# Ring_3_B.net
KiCad netlist of a schematic drawn in Altium Designer
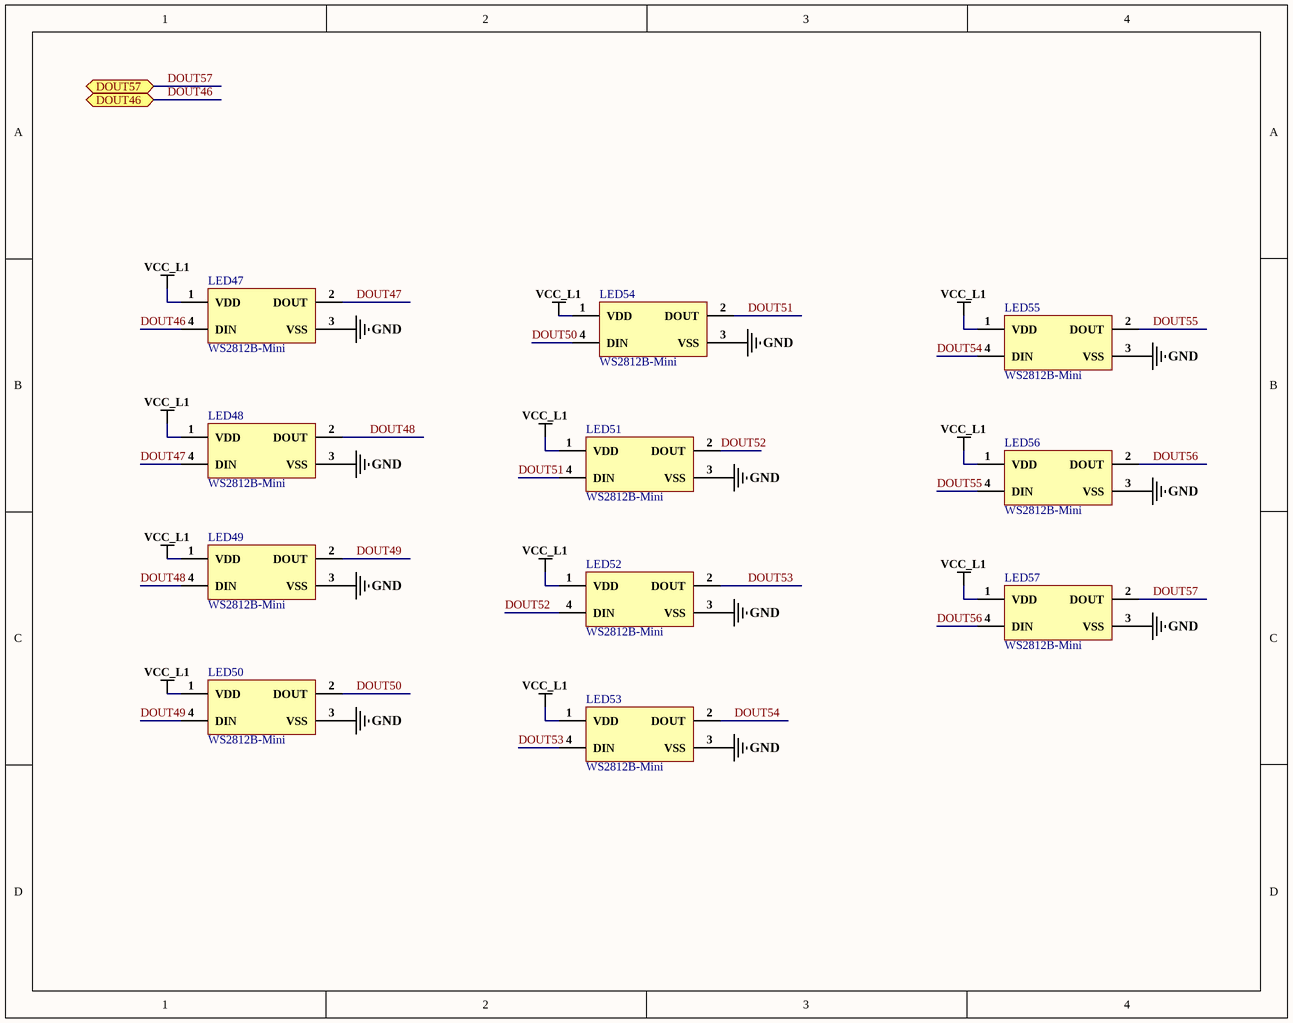
[diagram p0: Ring 3_B.SchDoc]

(export (version "E")
  (design (tool "Eeschema 10.0.6"))
  (components
    (comp (ref "LED47")
      (value "WS2812B-Mini")
      (footprint "WS2812B-Mini")
      (description "SMD,3.5x3.5mm Light Emitting Diodes (LED) RoHS")
      (fields (field (name "MANUFACTURER") "Worldsemi"))
      (libsource (lib "TT_IntLib") (part "WS2812B-Mini"))
    )
    (comp (ref "LED48")
      (value "WS2812B-Mini")
      (footprint "WS2812B-Mini")
      (description "SMD,3.5x3.5mm Light Emitting Diodes (LED) RoHS")
      (fields (field (name "MANUFACTURER") "Worldsemi"))
      (libsource (lib "TT_IntLib") (part "WS2812B-Mini"))
    )
    (comp (ref "LED49")
      (value "WS2812B-Mini")
      (footprint "WS2812B-Mini")
      (description "SMD,3.5x3.5mm Light Emitting Diodes (LED) RoHS")
      (fields (field (name "MANUFACTURER") "Worldsemi"))
      (libsource (lib "TT_IntLib") (part "WS2812B-Mini"))
    )
    (comp (ref "LED50")
      (value "WS2812B-Mini")
      (footprint "WS2812B-Mini")
      (description "SMD,3.5x3.5mm Light Emitting Diodes (LED) RoHS")
      (fields (field (name "MANUFACTURER") "Worldsemi"))
      (libsource (lib "TT_IntLib") (part "WS2812B-Mini"))
    )
    (comp (ref "LED51")
      (value "WS2812B-Mini")
      (footprint "WS2812B-Mini")
      (description "SMD,3.5x3.5mm Light Emitting Diodes (LED) RoHS")
      (fields (field (name "MANUFACTURER") "Worldsemi"))
      (libsource (lib "TT_IntLib") (part "WS2812B-Mini"))
    )
    (comp (ref "LED52")
      (value "WS2812B-Mini")
      (footprint "WS2812B-Mini")
      (description "SMD,3.5x3.5mm Light Emitting Diodes (LED) RoHS")
      (fields (field (name "MANUFACTURER") "Worldsemi"))
      (libsource (lib "TT_IntLib") (part "WS2812B-Mini"))
    )
    (comp (ref "LED53")
      (value "WS2812B-Mini")
      (footprint "WS2812B-Mini")
      (description "SMD,3.5x3.5mm Light Emitting Diodes (LED) RoHS")
      (fields (field (name "MANUFACTURER") "Worldsemi"))
      (libsource (lib "TT_IntLib") (part "WS2812B-Mini"))
    )
    (comp (ref "LED54")
      (value "WS2812B-Mini")
      (footprint "WS2812B-Mini")
      (description "SMD,3.5x3.5mm Light Emitting Diodes (LED) RoHS")
      (fields (field (name "MANUFACTURER") "Worldsemi"))
      (libsource (lib "TT_IntLib") (part "WS2812B-Mini"))
    )
    (comp (ref "LED55")
      (value "WS2812B-Mini")
      (footprint "WS2812B-Mini")
      (description "SMD,3.5x3.5mm Light Emitting Diodes (LED) RoHS")
      (fields (field (name "MANUFACTURER") "Worldsemi"))
      (libsource (lib "TT_IntLib") (part "WS2812B-Mini"))
    )
    (comp (ref "LED56")
      (value "WS2812B-Mini")
      (footprint "WS2812B-Mini")
      (description "SMD,3.5x3.5mm Light Emitting Diodes (LED) RoHS")
      (fields (field (name "MANUFACTURER") "Worldsemi"))
      (libsource (lib "TT_IntLib") (part "WS2812B-Mini"))
    )
    (comp (ref "LED57")
      (value "WS2812B-Mini")
      (footprint "WS2812B-Mini")
      (description "SMD,3.5x3.5mm Light Emitting Diodes (LED) RoHS")
      (fields (field (name "MANUFACTURER") "Worldsemi"))
      (libsource (lib "TT_IntLib") (part "WS2812B-Mini"))
    )
  )
  (nets
    (net (code "1") (name "/DOUT46") (class "Default")
      (node (ref "LED47") (pin "4") (pinfunction "DIN_4") (pintype "passive"))
    )
    (net (code "2") (name "/DOUT47") (class "Default")
      (node (ref "LED47") (pin "2") (pinfunction "DOUT_2") (pintype "passive"))
      (node (ref "LED48") (pin "4") (pinfunction "DIN_4") (pintype "passive"))
    )
    (net (code "3") (name "/DOUT48") (class "Default")
      (node (ref "LED48") (pin "2") (pinfunction "DOUT_2") (pintype "passive"))
      (node (ref "LED49") (pin "4") (pinfunction "DIN_4") (pintype "passive"))
    )
    (net (code "4") (name "/DOUT49") (class "Default")
      (node (ref "LED49") (pin "2") (pinfunction "DOUT_2") (pintype "passive"))
      (node (ref "LED50") (pin "4") (pinfunction "DIN_4") (pintype "passive"))
    )
    (net (code "5") (name "/DOUT50") (class "Default")
      (node (ref "LED50") (pin "2") (pinfunction "DOUT_2") (pintype "passive"))
      (node (ref "LED54") (pin "4") (pinfunction "DIN_4") (pintype "passive"))
    )
    (net (code "6") (name "/DOUT51") (class "Default")
      (node (ref "LED51") (pin "4") (pinfunction "DIN_4") (pintype "passive"))
      (node (ref "LED54") (pin "2") (pinfunction "DOUT_2") (pintype "passive"))
    )
    (net (code "7") (name "/DOUT52") (class "Default")
      (node (ref "LED51") (pin "2") (pinfunction "DOUT_2") (pintype "passive"))
      (node (ref "LED52") (pin "4") (pinfunction "DIN_4") (pintype "passive"))
    )
    (net (code "8") (name "/DOUT53") (class "Default")
      (node (ref "LED52") (pin "2") (pinfunction "DOUT_2") (pintype "passive"))
      (node (ref "LED53") (pin "4") (pinfunction "DIN_4") (pintype "passive"))
    )
    (net (code "9") (name "/DOUT54") (class "Default")
      (node (ref "LED53") (pin "2") (pinfunction "DOUT_2") (pintype "passive"))
      (node (ref "LED55") (pin "4") (pinfunction "DIN_4") (pintype "passive"))
    )
    (net (code "10") (name "/DOUT55") (class "Default")
      (node (ref "LED55") (pin "2") (pinfunction "DOUT_2") (pintype "passive"))
      (node (ref "LED56") (pin "4") (pinfunction "DIN_4") (pintype "passive"))
    )
    (net (code "11") (name "/DOUT56") (class "Default")
      (node (ref "LED56") (pin "2") (pinfunction "DOUT_2") (pintype "passive"))
      (node (ref "LED57") (pin "4") (pinfunction "DIN_4") (pintype "passive"))
    )
    (net (code "12") (name "/DOUT57") (class "Default")
      (node (ref "LED57") (pin "2") (pinfunction "DOUT_2") (pintype "passive"))
    )
    (net (code "13") (name "GND") (class "Default")
      (node (ref "LED47") (pin "3") (pinfunction "VSS_3") (pintype "passive"))
      (node (ref "LED48") (pin "3") (pinfunction "VSS_3") (pintype "passive"))
      (node (ref "LED49") (pin "3") (pinfunction "VSS_3") (pintype "passive"))
      (node (ref "LED50") (pin "3") (pinfunction "VSS_3") (pintype "passive"))
      (node (ref "LED51") (pin "3") (pinfunction "VSS_3") (pintype "passive"))
      (node (ref "LED52") (pin "3") (pinfunction "VSS_3") (pintype "passive"))
      (node (ref "LED53") (pin "3") (pinfunction "VSS_3") (pintype "passive"))
      (node (ref "LED54") (pin "3") (pinfunction "VSS_3") (pintype "passive"))
      (node (ref "LED55") (pin "3") (pinfunction "VSS_3") (pintype "passive"))
      (node (ref "LED56") (pin "3") (pinfunction "VSS_3") (pintype "passive"))
      (node (ref "LED57") (pin "3") (pinfunction "VSS_3") (pintype "passive"))
    )
    (net (code "14") (name "VCC_L1") (class "Default")
      (node (ref "LED47") (pin "1") (pinfunction "VDD_1") (pintype "passive"))
      (node (ref "LED48") (pin "1") (pinfunction "VDD_1") (pintype "passive"))
      (node (ref "LED49") (pin "1") (pinfunction "VDD_1") (pintype "passive"))
      (node (ref "LED50") (pin "1") (pinfunction "VDD_1") (pintype "passive"))
      (node (ref "LED51") (pin "1") (pinfunction "VDD_1") (pintype "passive"))
      (node (ref "LED52") (pin "1") (pinfunction "VDD_1") (pintype "passive"))
      (node (ref "LED53") (pin "1") (pinfunction "VDD_1") (pintype "passive"))
      (node (ref "LED54") (pin "1") (pinfunction "VDD_1") (pintype "passive"))
      (node (ref "LED55") (pin "1") (pinfunction "VDD_1") (pintype "passive"))
      (node (ref "LED56") (pin "1") (pinfunction "VDD_1") (pintype "passive"))
      (node (ref "LED57") (pin "1") (pinfunction "VDD_1") (pintype "passive"))
    )
  )
)
